# conn_isouart.net
KiCad netlist of a schematic drawn in Altium Designer
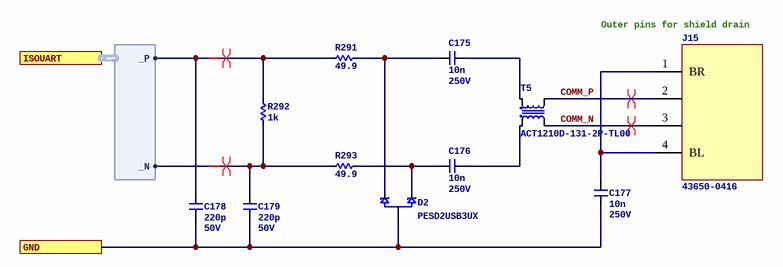
[diagram p0: conn_isouart.SchDoc]

(export (version "E")
  (design (tool "Eeschema 10.0.6"))
  (components
    (comp (ref "C175")
      (value "GRM21B5C2E103JWAAL")
      (footprint "C0805")
      (fields
        (field (name "CAPACITANCE") "10n")
        (field (name "MANUFACTURER") "Murata Electronics")
        (field (name "VOLTAGE RATING") "250V")
      )
      (libsource (lib "database") (part "__template_cap"))
    )
    (comp (ref "C176")
      (value "GRM21B5C2E103JWAAL")
      (footprint "C0805")
      (fields
        (field (name "CAPACITANCE") "10n")
        (field (name "MANUFACTURER") "Murata Electronics")
        (field (name "VOLTAGE RATING") "250V")
      )
      (libsource (lib "database") (part "__template_cap"))
    )
    (comp (ref "C177")
      (value "GRM21B5C2E103JWAAL")
      (footprint "C0805")
      (fields
        (field (name "CAPACITANCE") "10n")
        (field (name "MANUFACTURER") "Murata Electronics")
        (field (name "VOLTAGE RATING") "250V")
      )
      (libsource (lib "database") (part "__template_cap"))
    )
    (comp (ref "C178")
      (value "GRM1555C1H221JA01D")
      (footprint "C0402")
      (fields
        (field (name "CAPACITANCE") "220p")
        (field (name "MANUFACTURER") "Murata Electronics")
        (field (name "VOLTAGE RATING") "50V")
      )
      (libsource (lib "database") (part "__template_cap"))
    )
    (comp (ref "C179")
      (value "GRM1555C1H221JA01D")
      (footprint "C0402")
      (fields
        (field (name "CAPACITANCE") "220p")
        (field (name "MANUFACTURER") "Murata Electronics")
        (field (name "VOLTAGE RATING") "50V")
      )
      (libsource (lib "database") (part "__template_cap"))
    )
    (comp (ref "D2")
      (value "PESD2USB3UX")
      (footprint "3SOT23")
      (description "DIODE ESD USB SOT-23")
      (fields (field (name "MANUFACTURER") "Nexperia USA Inc."))
      (libsource (lib "SSCP") (part "TVS_PESD2USB3UX-T"))
    )
    (comp (ref "J15")
      (value "43650-0416")
      (footprint "MOLEX_MICROFIT_0436500416")
      (description "Connector Header Through Hole 4 position 0.118\" (3.00mm)")
      (fields (field (name "MANUFACTURER") "Molex"))
      (libsource (lib "SSCP") (part "CONN_MOLEX_MICROFIT_4POS_VERT_43650-0416"))
    )
    (comp (ref "R291")
      (value "49.9")
      (footprint "R0402")
      (fields
        (field (name "MANUFACTURER PART NUMBER") "0402WGF499JTCE")
        (field (name "MANUFACTURER") "UNI-ROYAL(Uniroyal Elec)")
        (field (name "TOLERANCE") "1%")
      )
      (libsource (lib "database") (part "__template_resistor"))
    )
    (comp (ref "R292")
      (value "1k")
      (footprint "R0402")
      (fields
        (field (name "MANUFACTURER PART NUMBER") "0402WGF1001TCE")
        (field (name "MANUFACTURER") "UNI-ROYAL(Uniroyal Elec)")
        (field (name "TOLERANCE") "1%")
      )
      (libsource (lib "database") (part "__template_resistor"))
    )
    (comp (ref "R293")
      (value "49.9")
      (footprint "R0402")
      (fields
        (field (name "MANUFACTURER PART NUMBER") "0402WGF499JTCE")
        (field (name "MANUFACTURER") "UNI-ROYAL(Uniroyal Elec)")
        (field (name "TOLERANCE") "1%")
      )
      (libsource (lib "database") (part "__template_resistor"))
    )
    (comp (ref "T5")
      (value "ACT1210D-131-2P-TL00")
      (footprint "CHOKE_ACT1210D-131-2P-TL00")
      (description "130 µH @ 100 kHz 2 Line Common Mode Choke Surface Mount 6.7 kOhms @ 10 MHz 115mA DCR 3.5Ohm")
      (fields (field (name "MANUFACTURER") "TDK Corporation"))
      (libsource (lib "SSCP") (part "CHOKE_ACT1210D-131-2P-TL00"))
    )
  )
  (nets
    (net (code "2") (name "/COMM_N") (class "Default")
      (node (ref "J15") (pin "3") (pintype "passive"))
      (node (ref "T5") (pin "4") (pintype "passive"))
    )
    (net (code "3") (name "/COMM_P") (class "Default")
      (node (ref "J15") (pin "2") (pintype "passive"))
      (node (ref "T5") (pin "3") (pintype "passive"))
    )
    (net (code "4") (name "/GND") (class "Default")
      (node (ref "C177") (pin "2") (pintype "passive"))
      (node (ref "C178") (pin "2") (pintype "passive"))
      (node (ref "C179") (pin "2") (pintype "passive"))
      (node (ref "D2") (pin "3") (pintype "passive"))
    )
    (net (code "6") (name "Net-(C175-Pad1)") (class "Default")
      (node (ref "C175") (pin "1") (pintype "passive"))
      (node (ref "D2") (pin "2") (pintype "passive"))
      (node (ref "R291") (pin "2") (pintype "passive"))
    )
    (net (code "7") (name "Net-(C175-Pad2)") (class "Default")
      (node (ref "C175") (pin "2") (pintype "passive"))
      (node (ref "T5") (pin "2") (pintype "passive"))
    )
    (net (code "8") (name "Net-(C176-Pad1)") (class "Default")
      (node (ref "C176") (pin "1") (pintype "passive"))
      (node (ref "D2") (pin "1") (pintype "passive"))
      (node (ref "R293") (pin "2") (pintype "passive"))
    )
    (net (code "9") (name "Net-(C176-Pad2)") (class "Default")
      (node (ref "C176") (pin "2") (pintype "passive"))
      (node (ref "T5") (pin "1") (pintype "passive"))
    )
    (net (code "10") (name "Net-(C178-Pad1)") (class "Default")
      (node (ref "C178") (pin "1") (pintype "passive"))
      (node (ref "R291") (pin "1") (pintype "passive"))
      (node (ref "R292") (pin "2") (pintype "passive"))
    )
    (net (code "11") (name "Net-(C179-Pad1)") (class "Default")
      (node (ref "C179") (pin "1") (pintype "passive"))
      (node (ref "R292") (pin "1") (pintype "passive"))
      (node (ref "R293") (pin "1") (pintype "passive"))
    )
    (net (code "12") (name "Net-(J15-BL)") (class "Default")
      (node (ref "C177") (pin "1") (pintype "passive"))
      (node (ref "J15") (pin "1") (pinfunction "BR_1") (pintype "passive"))
      (node (ref "J15") (pin "4") (pinfunction "BL_4") (pintype "passive"))
    )
  )
)
